# smd.net
KiCad netlist of a schematic drawn in EAGLE
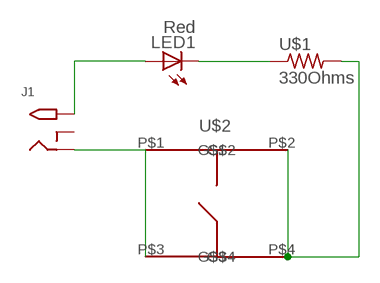
[diagram p0: schematic, sheet 1]

(export (version "E")
  (design (tool "Eeschema 10.0.6"))
  (components
    (comp (ref "J1")
      (value "2.1MMJACKTHM")
      (footprint "eagle-import:PJ-102A")
      (libsource (lib "eagle-import") (part "2.1MMJACKTHM"))
    )
    (comp (ref "LED1")
      (value "Red")
      (footprint "eagle-import:LED5MM")
      (libsource (lib "eagle-import") (part "LED5MM"))
    )
    (comp (ref "U$1")
      (value "330Ohms")
      (footprint "eagle-import:RESAD1160W55L680D260_HS")
      (libsource (lib "eagle-import") (part "RESISTORTH-1/4W-CARBON"))
    )
    (comp (ref "U$2")
      (value "BUTTON-TACTILE-SQUARE")
      (footprint "eagle-import:BUTTON-TACTILE-SQUARE")
      (libsource (lib "eagle-import") (part "BUTTON-TACTILE-SQUARE"))
    )
  )
  (nets
    (net (code "1") (name "Net-(J1-PadTIP)") (class "Default")
      (node (ref "J1") (pin "TIP") (pinfunction "TIP_TIP") (pintype "bidirectional"))
      (node (ref "LED1") (pin "A") (pinfunction "A_A") (pintype "passive"))
    )
    (net (code "2") (name "Net-(LED1-C)") (class "Default")
      (node (ref "LED1") (pin "K") (pinfunction "C_K") (pintype "passive"))
      (node (ref "U$1") (pin "1") (pinfunction "1_1") (pintype "passive"))
    )
    (net (code "3") (name "Net-(U$2-G$1)") (class "Default")
      (node (ref "J1") (pin "RING") (pinfunction "RING_RING") (pintype "bidirectional"))
      (node (ref "U$2") (pin "P$1") (pinfunction "G$1_P$1") (pintype "passive"))
      (node (ref "U$2") (pin "P$3") (pinfunction "G$3_P$3") (pintype "passive"))
    )
    (net (code "4") (name "Net-(U$2-G$2)") (class "Default")
      (node (ref "U$1") (pin "2") (pinfunction "2_2") (pintype "passive"))
      (node (ref "U$2") (pin "P$2") (pinfunction "G$2_P$2") (pintype "passive"))
      (node (ref "U$2") (pin "P$4") (pinfunction "G$4_P$4") (pintype "passive"))
    )
    (net (code "5") (name "unconnected-(J1-PadRING_SW)") (class "Default")
      (node (ref "J1") (pin "RING_SW") (pinfunction "RING_SW_RING_SW") (pintype "bidirectional"))
    )
  )
)
